# esp_dht.net
KiCad netlist of a schematic drawn in EAGLE
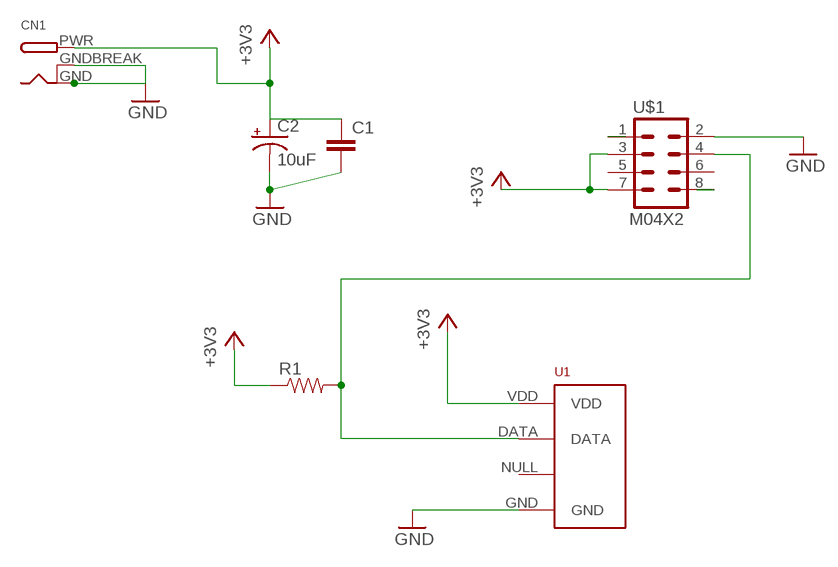
[diagram p0: schematic, sheet 1]

(export (version "E")
  (design (tool "Eeschema 10.0.6"))
  (components
    (comp (ref "C1")
      (value "CAPPTH")
      (footprint "eagle-import:CAP-PTH-SMALL")
      (libsource (lib "eagle-import") (part "CAPPTH"))
    )
    (comp (ref "C2")
      (value "10uF")
      (footprint "eagle-import:CPOL-RADIAL-10UF-25V")
      (libsource (lib "eagle-import") (part "CAP_POLPTH2"))
    )
    (comp (ref "CN1")
      (value "DCBARRELPTH")
      (footprint "eagle-import:DCJACK_2MM_PTH")
      (libsource (lib "eagle-import") (part "DCBARRELPTH"))
    )
    (comp (ref "R1")
      (value "RESISTORPTH-1/4W")
      (footprint "eagle-import:AXIAL-0.4")
      (libsource (lib "eagle-import") (part "RESISTORPTH-1/4W"))
    )
    (comp (ref "U$1")
      (value "M04X2")
      (footprint "eagle-import:2X4")
      (libsource (lib "eagle-import") (part "M04X2"))
    )
    (comp (ref "U1")
      (value "RHT03_DHT-22_AM2302RA")
      (footprint "eagle-import:RHT03_DHT-22_RA")
      (libsource (lib "eagle-import") (part "RHT03_DHT-22_AM2302RA"))
    )
  )
  (nets
    (net (code "1") (name "+3V3") (class "Default")
      (node (ref "C1") (pin "1") (pinfunction "1_1") (pintype "passive"))
      (node (ref "C2") (pin "1") (pinfunction "+_1") (pintype "passive"))
      (node (ref "CN1") (pin "PWR") (pinfunction "PWR_PWR") (pintype "power_in"))
      (node (ref "R1") (pin "P$1") (pinfunction "1_P$1") (pintype "passive"))
      (node (ref "U$1") (pin "3") (pinfunction "3_3") (pintype "passive"))
      (node (ref "U$1") (pin "7") (pinfunction "7_7") (pintype "passive"))
      (node (ref "U1") (pin "VDD") (pinfunction "VDD_VDD") (pintype "power_in"))
    )
    (net (code "2") (name "GND") (class "Default")
      (node (ref "C1") (pin "2") (pinfunction "2_2") (pintype "passive"))
      (node (ref "C2") (pin "2") (pinfunction "-_2") (pintype "passive"))
      (node (ref "CN1") (pin "GND") (pinfunction "GND_GND") (pintype "power_in"))
      (node (ref "CN1") (pin "GNDBREAK") (pinfunction "GNDBREAK_GNDBREAK") (pintype "power_in"))
      (node (ref "U$1") (pin "2") (pinfunction "2_2") (pintype "passive"))
      (node (ref "U1") (pin "GND") (pinfunction "GND_GND") (pintype "power_in"))
    )
    (net (code "3") (name "Net-(R1-2)") (class "Default")
      (node (ref "R1") (pin "P$2") (pinfunction "2_P$2") (pintype "passive"))
      (node (ref "U$1") (pin "4") (pinfunction "4_4") (pintype "passive"))
      (node (ref "U1") (pin "DATA") (pinfunction "DATA_DATA") (pintype "bidirectional"))
    )
    (net (code "4") (name "unconnected-(U$1-Pad1)") (class "Default")
      (node (ref "U$1") (pin "1") (pinfunction "1_1") (pintype "passive"))
    )
    (net (code "5") (name "unconnected-(U$1-Pad5)") (class "Default")
      (node (ref "U$1") (pin "5") (pinfunction "5_5") (pintype "passive"))
    )
    (net (code "6") (name "unconnected-(U$1-Pad6)") (class "Default")
      (node (ref "U$1") (pin "6") (pinfunction "6_6") (pintype "passive"))
    )
    (net (code "7") (name "unconnected-(U$1-Pad8)") (class "Default")
      (node (ref "U$1") (pin "8") (pinfunction "8_8") (pintype "passive"))
    )
    (net (code "8") (name "unconnected-(U1-PadNULL)") (class "Default")
      (node (ref "U1") (pin "NULL") (pinfunction "NULL_NULL") (pintype "no_connect"))
    )
  )
)
